# 14_WIFI_BT.net
KiCad netlist of a schematic drawn in Altium Designer
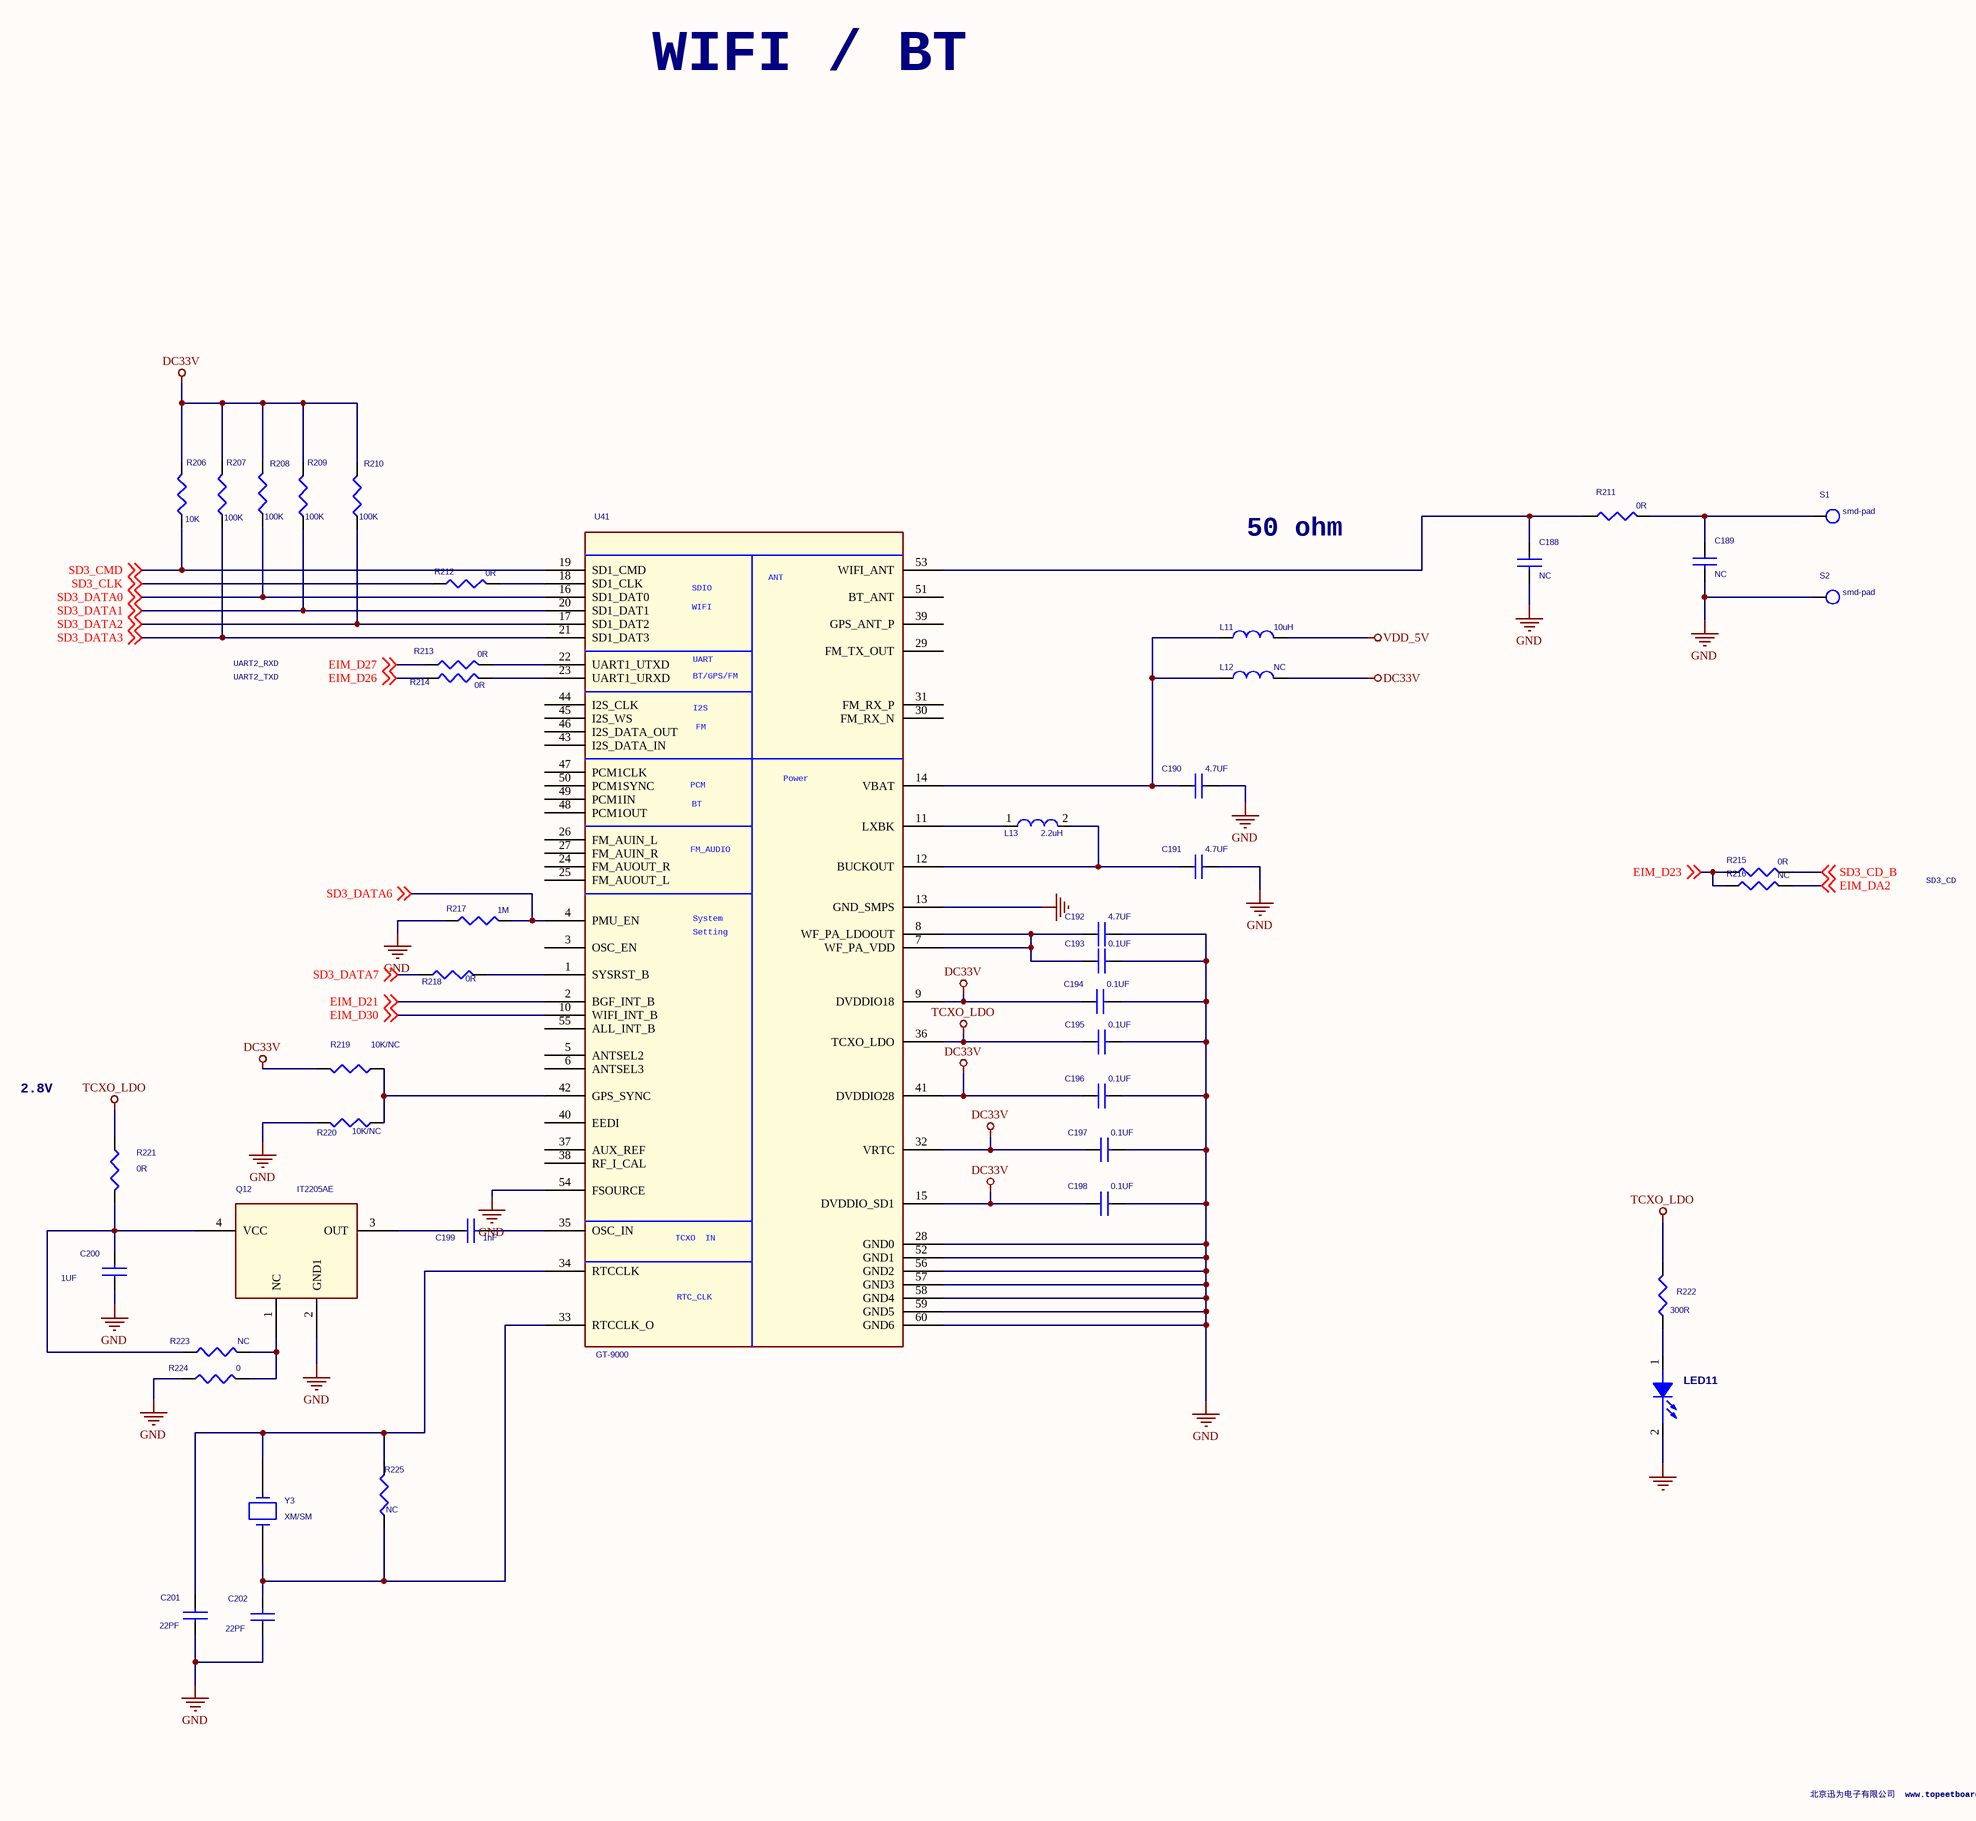
[diagram p0: 14 WIFI BT.SchDoc]

(export (version "E")
  (design (tool "Eeschema 10.0.6"))
  (components
    (comp (ref "C188") (value "NC") (footprint "C1005") (libsource (lib "*") (part "C1005_Dup1")))
    (comp (ref "C189") (value "NC") (footprint "C1005") (libsource (lib "*") (part "C1005_Dup1")))
    (comp (ref "C190") (value "4.7UF") (footprint "C1005") (libsource (lib "*") (part "C1005_Dup1")))
    (comp (ref "C191") (value "4.7UF") (footprint "C1005") (libsource (lib "*") (part "C1005_Dup1")))
    (comp (ref "C192") (value "4.7UF") (footprint "C1005") (libsource (lib "*") (part "C1005_Dup1")))
    (comp (ref "C193") (value "0.1UF") (footprint "C1005") (libsource (lib "*") (part "C1005_Dup1")))
    (comp (ref "C194") (value "0.1UF") (footprint "C1005") (libsource (lib "*") (part "C1005_Dup1")))
    (comp (ref "C195") (value "0.1UF") (footprint "C1005") (libsource (lib "*") (part "C1005_Dup1")))
    (comp (ref "C196") (value "0.1UF") (footprint "C1005") (libsource (lib "*") (part "C1005_Dup1")))
    (comp (ref "C197") (value "0.1UF") (footprint "C1005") (libsource (lib "*") (part "C1005_Dup1")))
    (comp (ref "C198") (value "0.1UF") (footprint "C1005") (libsource (lib "*") (part "C1005_Dup1")))
    (comp (ref "C199") (value "1nF") (footprint "C1005") (libsource (lib "*") (part "C1005_Dup1")))
    (comp (ref "C200") (value "1UF") (footprint "C1005") (libsource (lib "*") (part "C1005_Dup1")))
    (comp (ref "C201") (value "22PF") (footprint "C1005") (libsource (lib "*") (part "C1005_Dup1")))
    (comp (ref "C202") (value "22PF") (footprint "C1005") (libsource (lib "*") (part "C1005_Dup1")))
    (comp (ref "L11") (value "10uH") (footprint "LQH32C") (libsource (lib "*") (part "LQH32C_0")))
    (comp (ref "L12") (value "NC") (footprint "LQH32C") (libsource (lib "*") (part "LQH32C_0")))
    (comp (ref "L13") (value "2.2uH") (footprint "LQH32C") (libsource (lib "*") (part "LQH32C_0_Dup1")))
    (comp (ref "LED11")
      (value "LED-Red (SMD 2012)")
      (footprint "LED-3216")
      (libsource (lib "*") (part "LED-RED_SMD_1"))
    )
    (comp (ref "Q12") (value "IT2205AE") (libsource (lib "*") (part "IT2205AE_1")))
    (comp (ref "R206") (value "10K") (footprint "R1005") (libsource (lib "*") (part "R1005_0_Dup1")))
    (comp (ref "R207") (value "100K") (footprint "R1005") (libsource (lib "*") (part "R1005_0_Dup1")))
    (comp (ref "R208") (value "100K") (footprint "R1005") (libsource (lib "*") (part "R1005_0_Dup1")))
    (comp (ref "R209") (value "100K") (footprint "R1005") (libsource (lib "*") (part "R1005_0_Dup1")))
    (comp (ref "R210") (value "100K") (footprint "R1005") (libsource (lib "*") (part "R1005_0_Dup1")))
    (comp (ref "R211") (value "0R") (footprint "R1005") (libsource (lib "*") (part "R1005_0_Dup1")))
    (comp (ref "R212") (value "0R") (footprint "R1005") (libsource (lib "*") (part "R1005_0_Dup1")))
    (comp (ref "R213") (value "0R") (footprint "R1005") (libsource (lib "*") (part "R1005_0_Dup1")))
    (comp (ref "R214") (value "0R") (footprint "R1005") (libsource (lib "*") (part "R1005_0_Dup1")))
    (comp (ref "R215") (value "0R") (footprint "R1005") (libsource (lib "*") (part "R1005_0_Dup1")))
    (comp (ref "R216") (value "NC") (footprint "R1005") (libsource (lib "*") (part "R1005_0_Dup1")))
    (comp (ref "R217") (value "1M") (footprint "R1005") (libsource (lib "*") (part "R1005_0_Dup1")))
    (comp (ref "R218") (value "0R") (footprint "R1005") (libsource (lib "*") (part "R1005_0_Dup1")))
    (comp (ref "R219") (value "10K/NC") (footprint "R1005") (libsource (lib "*") (part "R1005_0_Dup1")))
    (comp (ref "R220") (value "10K/NC") (footprint "R1005") (libsource (lib "*") (part "R1005_0_Dup1")))
    (comp (ref "R221") (value "0R") (footprint "R1005") (libsource (lib "*") (part "R1005_0_Dup1")))
    (comp (ref "R222") (value "300R") (footprint "R1005") (libsource (lib "*") (part "R1005_0_Dup2")))
    (comp (ref "R223") (value "NC") (footprint "R1005") (libsource (lib "*") (part "R1005_0_Dup1")))
    (comp (ref "R224") (value "0") (footprint "R1005") (libsource (lib "*") (part "R1005_0_Dup1")))
    (comp (ref "R225") (value "NC") (footprint "R1005") (libsource (lib "*") (part "R1005_0_Dup1")))
    (comp (ref "S1") (value "smd-pad") (footprint "TP_08") (libsource (lib "*") (part "TP_P0_0.8_D0")))
    (comp (ref "S2") (value "smd-pad") (footprint "TP_08") (libsource (lib "*") (part "TP_P0_0.8_D0")))
    (comp (ref "U41") (value "GT-9000") (libsource (lib "*") (part "GT-9000_0")))
    (comp (ref "Y3") (value "XM/SM") (libsource (lib "*") (part "XM/SM")))
  )
  (nets
    (net (code "1") (name "DC33V") (class "Default")
      (node (ref "C194") (pin "1") (pinfunction "1_1") (pintype "passive"))
      (node (ref "C196") (pin "1") (pinfunction "1_1") (pintype "passive"))
      (node (ref "C197") (pin "1") (pinfunction "1_1") (pintype "passive"))
      (node (ref "C198") (pin "1") (pinfunction "1_1") (pintype "passive"))
      (node (ref "L12") (pin "2") (pinfunction "2_2") (pintype "passive"))
      (node (ref "R206") (pin "2") (pinfunction "2_2") (pintype "passive"))
      (node (ref "R207") (pin "2") (pinfunction "2_2") (pintype "passive"))
      (node (ref "R208") (pin "2") (pinfunction "2_2") (pintype "passive"))
      (node (ref "R209") (pin "2") (pinfunction "2_2") (pintype "passive"))
      (node (ref "R210") (pin "2") (pinfunction "2_2") (pintype "passive"))
      (node (ref "R219") (pin "2") (pinfunction "2_2") (pintype "passive"))
      (node (ref "U41") (pin "15") (pinfunction "DVDDIO_SD1_15") (pintype "passive"))
      (node (ref "U41") (pin "32") (pinfunction "VRTC_32") (pintype "passive"))
      (node (ref "U41") (pin "41") (pinfunction "DVDDIO28_41") (pintype "passive"))
      (node (ref "U41") (pin "9") (pinfunction "DVDDIO18_9") (pintype "passive"))
    )
    (net (code "2") (name "EIM_D21") (class "Default")
      (node (ref "U41") (pin "2") (pinfunction "BGF_INT_B_2") (pintype "passive"))
    )
    (net (code "3") (name "EIM_D23") (class "Default")
      (node (ref "R215") (pin "1") (pinfunction "1_1") (pintype "passive"))
      (node (ref "R216") (pin "1") (pinfunction "1_1") (pintype "passive"))
    )
    (net (code "4") (name "EIM_D26") (class "Default")
      (node (ref "R214") (pin "1") (pinfunction "1_1") (pintype "passive"))
    )
    (net (code "5") (name "EIM_D27") (class "Default")
      (node (ref "R213") (pin "1") (pinfunction "1_1") (pintype "passive"))
    )
    (net (code "6") (name "EIM_D30") (class "Default")
      (node (ref "U41") (pin "10") (pinfunction "WIFI_INT_B_10") (pintype "passive"))
    )
    (net (code "7") (name "EIM_DA2") (class "Default")
      (node (ref "R216") (pin "2") (pinfunction "2_2") (pintype "passive"))
    )
    (net (code "8") (name "GND") (class "Default")
      (node (ref "C188") (pin "2") (pinfunction "2_2") (pintype "passive"))
      (node (ref "C189") (pin "2") (pinfunction "2_2") (pintype "passive"))
      (node (ref "C190") (pin "2") (pinfunction "2_2") (pintype "passive"))
      (node (ref "C191") (pin "2") (pinfunction "2_2") (pintype "passive"))
      (node (ref "C192") (pin "2") (pinfunction "2_2") (pintype "passive"))
      (node (ref "C193") (pin "2") (pinfunction "2_2") (pintype "passive"))
      (node (ref "C194") (pin "2") (pinfunction "2_2") (pintype "passive"))
      (node (ref "C195") (pin "2") (pinfunction "2_2") (pintype "passive"))
      (node (ref "C196") (pin "2") (pinfunction "2_2") (pintype "passive"))
      (node (ref "C197") (pin "2") (pinfunction "2_2") (pintype "passive"))
      (node (ref "C198") (pin "2") (pinfunction "2_2") (pintype "passive"))
      (node (ref "C200") (pin "1") (pinfunction "1_1") (pintype "passive"))
      (node (ref "C201") (pin "1") (pinfunction "1_1") (pintype "passive"))
      (node (ref "C202") (pin "1") (pinfunction "1_1") (pintype "passive"))
      (node (ref "LED11") (pin "2") (pinfunction "CATHODE_2") (pintype "passive"))
      (node (ref "Q12") (pin "2") (pinfunction "GND1_2") (pintype "passive"))
      (node (ref "R217") (pin "1") (pinfunction "1_1") (pintype "passive"))
      (node (ref "R220") (pin "2") (pinfunction "2_2") (pintype "passive"))
      (node (ref "R224") (pin "1") (pinfunction "1_1") (pintype "passive"))
      (node (ref "S2") (pin "1") (pinfunction "1_1") (pintype "passive"))
      (node (ref "U41") (pin "13") (pinfunction "GND_SMPS_13") (pintype "passive"))
      (node (ref "U41") (pin "28") (pinfunction "GND0_28") (pintype "passive"))
      (node (ref "U41") (pin "52") (pinfunction "GND1_52") (pintype "passive"))
      (node (ref "U41") (pin "54") (pinfunction "FSOURCE_54") (pintype "passive"))
      (node (ref "U41") (pin "56") (pinfunction "GND2_56") (pintype "passive"))
      (node (ref "U41") (pin "57") (pinfunction "GND3_57") (pintype "passive"))
      (node (ref "U41") (pin "58") (pinfunction "GND4_58") (pintype "passive"))
      (node (ref "U41") (pin "59") (pinfunction "GND5_59") (pintype "passive"))
      (node (ref "U41") (pin "60") (pinfunction "GND6_60") (pintype "passive"))
    )
    (net (code "9") (name "Net-(C189-Pad1)") (class "Default")
      (node (ref "C189") (pin "1") (pinfunction "1_1") (pintype "passive"))
      (node (ref "R211") (pin "2") (pinfunction "2_2") (pintype "passive"))
      (node (ref "S1") (pin "1") (pinfunction "1_1") (pintype "passive"))
    )
    (net (code "10") (name "Net-(LED11-ANODE)") (class "Default")
      (node (ref "LED11") (pin "1") (pinfunction "ANODE_1") (pintype "passive"))
      (node (ref "R222") (pin "1") (pinfunction "1_1") (pintype "passive"))
    )
    (net (code "11") (name "Net-(Q12-NC)") (class "Default")
      (node (ref "Q12") (pin "1") (pinfunction "NC_1") (pintype "passive"))
      (node (ref "R223") (pin "2") (pinfunction "2_2") (pintype "passive"))
      (node (ref "R224") (pin "2") (pinfunction "2_2") (pintype "passive"))
    )
    (net (code "12") (name "Net-(Q12-OUT)") (class "Default")
      (node (ref "C199") (pin "1") (pinfunction "1_1") (pintype "passive"))
      (node (ref "Q12") (pin "3") (pinfunction "OUT_3") (pintype "passive"))
    )
    (net (code "13") (name "Net-(Q12-VCC)") (class "Default")
      (node (ref "C200") (pin "2") (pinfunction "2_2") (pintype "passive"))
      (node (ref "Q12") (pin "4") (pinfunction "VCC_4") (pintype "passive"))
      (node (ref "R221") (pin "2") (pinfunction "2_2") (pintype "passive"))
      (node (ref "R223") (pin "1") (pinfunction "1_1") (pintype "passive"))
    )
    (net (code "14") (name "Net-(U41-BUCKOUT)") (class "Default")
      (node (ref "C191") (pin "1") (pinfunction "1_1") (pintype "passive"))
      (node (ref "L13") (pin "2") (pinfunction "2_2") (pintype "passive"))
      (node (ref "U41") (pin "12") (pinfunction "BUCKOUT_12") (pintype "passive"))
    )
    (net (code "15") (name "Net-(U41-GPS_SYNC)") (class "Default")
      (node (ref "R219") (pin "1") (pinfunction "1_1") (pintype "passive"))
      (node (ref "R220") (pin "1") (pinfunction "1_1") (pintype "passive"))
      (node (ref "U41") (pin "42") (pinfunction "GPS_SYNC_42") (pintype "passive"))
    )
    (net (code "16") (name "Net-(U41-LXBK)") (class "Default")
      (node (ref "L13") (pin "1") (pinfunction "1_1") (pintype "passive"))
      (node (ref "U41") (pin "11") (pinfunction "LXBK_11") (pintype "passive"))
    )
    (net (code "17") (name "Net-(U41-OSC_IN)") (class "Default")
      (node (ref "C199") (pin "2") (pinfunction "2_2") (pintype "passive"))
      (node (ref "U41") (pin "35") (pinfunction "OSC_IN_35") (pintype "passive"))
    )
    (net (code "18") (name "Net-(U41-RTCCLK)") (class "Default")
      (node (ref "C201") (pin "2") (pinfunction "2_2") (pintype "passive"))
      (node (ref "R225") (pin "2") (pinfunction "2_2") (pintype "passive"))
      (node (ref "U41") (pin "34") (pinfunction "RTCCLK_34") (pintype "passive"))
      (node (ref "Y3") (pin "2") (pinfunction "2_2") (pintype "passive"))
    )
    (net (code "19") (name "Net-(U41-RTCCLK_O)") (class "Default")
      (node (ref "C202") (pin "2") (pinfunction "2_2") (pintype "passive"))
      (node (ref "R225") (pin "1") (pinfunction "1_1") (pintype "passive"))
      (node (ref "U41") (pin "33") (pinfunction "RTCCLK_O_33") (pintype "passive"))
      (node (ref "Y3") (pin "1") (pinfunction "1_1") (pintype "passive"))
    )
    (net (code "20") (name "Net-(U41-SD1_CLK)") (class "Default")
      (node (ref "R212") (pin "2") (pinfunction "2_2") (pintype "passive"))
      (node (ref "U41") (pin "18") (pinfunction "SD1_CLK_18") (pintype "passive"))
    )
    (net (code "21") (name "Net-(U41-SYSRST_B)") (class "Default")
      (node (ref "R218") (pin "2") (pinfunction "2_2") (pintype "passive"))
      (node (ref "U41") (pin "1") (pinfunction "SYSRST_B_1") (pintype "passive"))
    )
    (net (code "22") (name "Net-(U41-UART1_URXD)") (class "Default")
      (node (ref "R214") (pin "2") (pinfunction "2_2") (pintype "passive"))
      (node (ref "U41") (pin "23") (pinfunction "UART1_URXD_23") (pintype "passive"))
    )
    (net (code "23") (name "Net-(U41-UART1_UTXD)") (class "Default")
      (node (ref "R213") (pin "2") (pinfunction "2_2") (pintype "passive"))
      (node (ref "U41") (pin "22") (pinfunction "UART1_UTXD_22") (pintype "passive"))
    )
    (net (code "24") (name "Net-(U41-VBAT)") (class "Default")
      (node (ref "C190") (pin "1") (pinfunction "1_1") (pintype "passive"))
      (node (ref "L11") (pin "1") (pinfunction "1_1") (pintype "passive"))
      (node (ref "L12") (pin "1") (pinfunction "1_1") (pintype "passive"))
      (node (ref "U41") (pin "14") (pinfunction "VBAT_14") (pintype "passive"))
    )
    (net (code "25") (name "Net-(U41-WF_PA_LDOOUT)") (class "Default")
      (node (ref "C192") (pin "1") (pinfunction "1_1") (pintype "passive"))
      (node (ref "C193") (pin "1") (pinfunction "1_1") (pintype "passive"))
      (node (ref "U41") (pin "7") (pinfunction "WF_PA_VDD_7") (pintype "passive"))
      (node (ref "U41") (pin "8") (pinfunction "WF_PA_LDOOUT_8") (pintype "passive"))
    )
    (net (code "26") (name "Net-(U41-WIFI_ANT)") (class "Default")
      (node (ref "C188") (pin "1") (pinfunction "1_1") (pintype "passive"))
      (node (ref "R211") (pin "1") (pinfunction "1_1") (pintype "passive"))
      (node (ref "U41") (pin "53") (pinfunction "WIFI_ANT_53") (pintype "passive"))
    )
    (net (code "27") (name "SD3_CD_B") (class "Default")
      (node (ref "R215") (pin "2") (pinfunction "2_2") (pintype "passive"))
    )
    (net (code "28") (name "SD3_CLK") (class "Default")
      (node (ref "R212") (pin "1") (pinfunction "1_1") (pintype "passive"))
    )
    (net (code "29") (name "SD3_CMD") (class "Default")
      (node (ref "R206") (pin "1") (pinfunction "1_1") (pintype "passive"))
      (node (ref "U41") (pin "19") (pinfunction "SD1_CMD_19") (pintype "passive"))
    )
    (net (code "30") (name "SD3_DATA0") (class "Default")
      (node (ref "R208") (pin "1") (pinfunction "1_1") (pintype "passive"))
      (node (ref "U41") (pin "16") (pinfunction "SD1_DAT0_16") (pintype "passive"))
    )
    (net (code "31") (name "SD3_DATA1") (class "Default")
      (node (ref "R209") (pin "1") (pinfunction "1_1") (pintype "passive"))
      (node (ref "U41") (pin "20") (pinfunction "SD1_DAT1_20") (pintype "passive"))
    )
    (net (code "32") (name "SD3_DATA2") (class "Default")
      (node (ref "R210") (pin "1") (pinfunction "1_1") (pintype "passive"))
      (node (ref "U41") (pin "17") (pinfunction "SD1_DAT2_17") (pintype "passive"))
    )
    (net (code "33") (name "SD3_DATA3") (class "Default")
      (node (ref "R207") (pin "1") (pinfunction "1_1") (pintype "passive"))
      (node (ref "U41") (pin "21") (pinfunction "SD1_DAT3_21") (pintype "passive"))
    )
    (net (code "34") (name "SD3_DATA6") (class "Default")
      (node (ref "R217") (pin "2") (pinfunction "2_2") (pintype "passive"))
      (node (ref "U41") (pin "4") (pinfunction "PMU_EN_4") (pintype "passive"))
    )
    (net (code "35") (name "SD3_DATA7") (class "Default")
      (node (ref "R218") (pin "1") (pinfunction "1_1") (pintype "passive"))
    )
    (net (code "36") (name "TCXO_LDO") (class "Default")
      (node (ref "C195") (pin "1") (pinfunction "1_1") (pintype "passive"))
      (node (ref "R221") (pin "1") (pinfunction "1_1") (pintype "passive"))
      (node (ref "R222") (pin "2") (pinfunction "2_2") (pintype "passive"))
      (node (ref "U41") (pin "36") (pinfunction "TCXO_LDO_36") (pintype "passive"))
    )
    (net (code "37") (name "VDD_5V") (class "Default")
      (node (ref "L11") (pin "2") (pinfunction "2_2") (pintype "passive"))
    )
    (net (code "38") (name "unconnected-(U41-ALL_INT_B-Pad55)") (class "Default")
      (node (ref "U41") (pin "55") (pinfunction "ALL_INT_B_55") (pintype "passive"))
    )
    (net (code "39") (name "unconnected-(U41-ANTSEL2-Pad5)") (class "Default")
      (node (ref "U41") (pin "5") (pinfunction "ANTSEL2_5") (pintype "passive"))
    )
    (net (code "40") (name "unconnected-(U41-ANTSEL3-Pad6)") (class "Default")
      (node (ref "U41") (pin "6") (pinfunction "ANTSEL3_6") (pintype "passive"))
    )
    (net (code "41") (name "unconnected-(U41-AUX_REF-Pad37)") (class "Default")
      (node (ref "U41") (pin "37") (pinfunction "AUX_REF_37") (pintype "passive"))
    )
    (net (code "42") (name "unconnected-(U41-BT_ANT-Pad51)") (class "Default")
      (node (ref "U41") (pin "51") (pinfunction "BT_ANT_51") (pintype "passive"))
    )
    (net (code "43") (name "unconnected-(U41-EEDI-Pad40)") (class "Default")
      (node (ref "U41") (pin "40") (pinfunction "EEDI_40") (pintype "passive"))
    )
    (net (code "44") (name "unconnected-(U41-FM_AUIN_L-Pad26)") (class "Default")
      (node (ref "U41") (pin "26") (pinfunction "FM_AUIN_L_26") (pintype "passive"))
    )
    (net (code "45") (name "unconnected-(U41-FM_AUIN_R-Pad27)") (class "Default")
      (node (ref "U41") (pin "27") (pinfunction "FM_AUIN_R_27") (pintype "passive"))
    )
    (net (code "46") (name "unconnected-(U41-FM_AUOUT_L-Pad25)") (class "Default")
      (node (ref "U41") (pin "25") (pinfunction "FM_AUOUT_L_25") (pintype "passive"))
    )
    (net (code "47") (name "unconnected-(U41-FM_AUOUT_R-Pad24)") (class "Default")
      (node (ref "U41") (pin "24") (pinfunction "FM_AUOUT_R_24") (pintype "passive"))
    )
    (net (code "48") (name "unconnected-(U41-FM_RX_N-Pad30)") (class "Default")
      (node (ref "U41") (pin "30") (pinfunction "FM_RX_N_30") (pintype "passive"))
    )
    (net (code "49") (name "unconnected-(U41-FM_RX_P-Pad31)") (class "Default")
      (node (ref "U41") (pin "31") (pinfunction "FM_RX_P_31") (pintype "passive"))
    )
    (net (code "50") (name "unconnected-(U41-FM_TX_OUT-Pad29)") (class "Default")
      (node (ref "U41") (pin "29") (pinfunction "FM_TX_OUT_29") (pintype "passive"))
    )
    (net (code "51") (name "unconnected-(U41-GPS_ANT_P-Pad39)") (class "Default")
      (node (ref "U41") (pin "39") (pinfunction "GPS_ANT_P_39") (pintype "passive"))
    )
    (net (code "52") (name "unconnected-(U41-I2S_CLK-Pad44)") (class "Default")
      (node (ref "U41") (pin "44") (pinfunction "I2S_CLK_44") (pintype "passive"))
    )
    (net (code "53") (name "unconnected-(U41-I2S_DATA_IN-Pad43)") (class "Default")
      (node (ref "U41") (pin "43") (pinfunction "I2S_DATA_IN_43") (pintype "passive"))
    )
    (net (code "54") (name "unconnected-(U41-I2S_DATA_OUT-Pad46)") (class "Default")
      (node (ref "U41") (pin "46") (pinfunction "I2S_DATA_OUT_46") (pintype "passive"))
    )
    (net (code "55") (name "unconnected-(U41-I2S_WS-Pad45)") (class "Default")
      (node (ref "U41") (pin "45") (pinfunction "I2S_WS_45") (pintype "passive"))
    )
    (net (code "56") (name "unconnected-(U41-OSC_EN-Pad3)") (class "Default")
      (node (ref "U41") (pin "3") (pinfunction "OSC_EN_3") (pintype "passive"))
    )
    (net (code "57") (name "unconnected-(U41-PCM1CLK-Pad47)") (class "Default")
      (node (ref "U41") (pin "47") (pinfunction "PCM1CLK_47") (pintype "passive"))
    )
    (net (code "58") (name "unconnected-(U41-PCM1IN-Pad49)") (class "Default")
      (node (ref "U41") (pin "49") (pinfunction "PCM1IN_49") (pintype "passive"))
    )
    (net (code "59") (name "unconnected-(U41-PCM1OUT-Pad48)") (class "Default")
      (node (ref "U41") (pin "48") (pinfunction "PCM1OUT_48") (pintype "passive"))
    )
    (net (code "60") (name "unconnected-(U41-PCM1SYNC-Pad50)") (class "Default")
      (node (ref "U41") (pin "50") (pinfunction "PCM1SYNC_50") (pintype "passive"))
    )
    (net (code "61") (name "unconnected-(U41-RF_I_CAL-Pad38)") (class "Default")
      (node (ref "U41") (pin "38") (pinfunction "RF_I_CAL_38") (pintype "passive"))
    )
  )
)
